# sb-sonata-headers1.net
KiCad netlist of a schematic drawn in Altium Designer
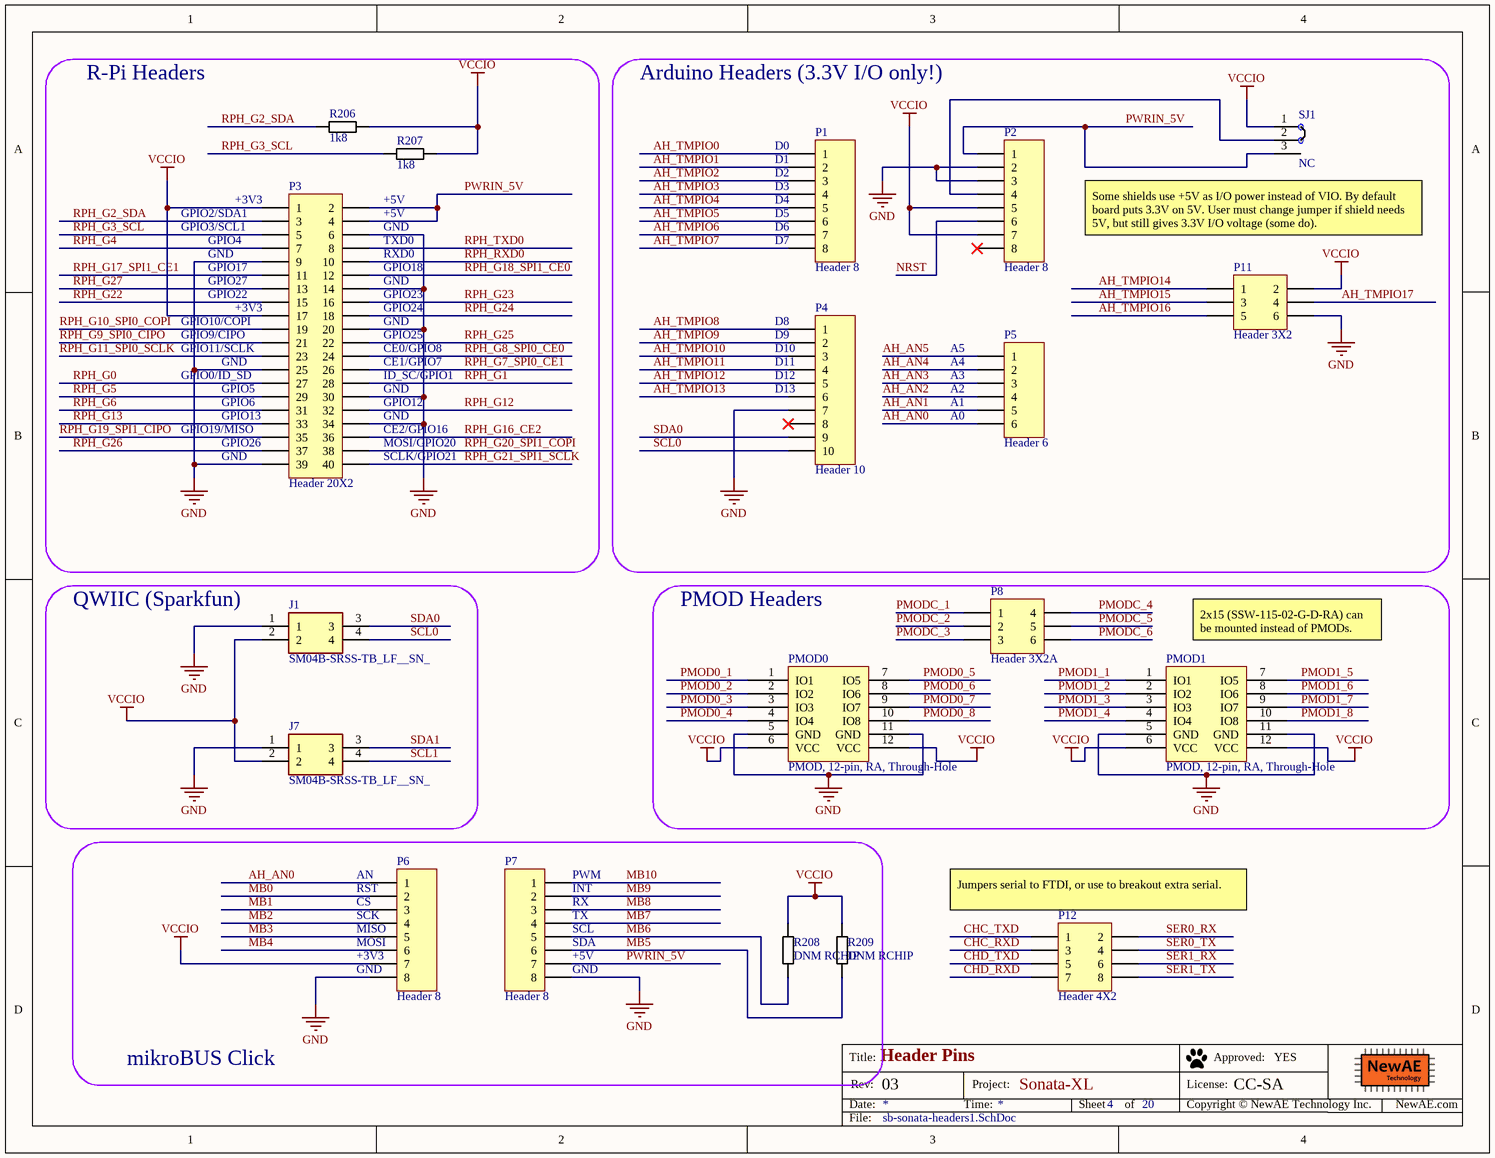
[diagram p0: sb-sonata-headers1.SchDoc]

(export (version "E")
  (design (tool "Eeschema 10.0.6"))
  (components
    (comp (ref "J1")
      (value "SM04B-SRSS-TB_LF__SN_")
      (footprint "SM04B-SRSS-TB(LFSN)")
      (description "Connector")
      (fields (field (name "MANUFACTURER_PART_NUMBER") "SM04B-SRSS-TB(LF)(SN)"))
      (libsource (lib "*") (part "SM04B-SRSS-TB_LF__SN_"))
    )
    (comp (ref "J7")
      (value "SM04B-SRSS-TB_LF__SN_")
      (footprint "SM04B-SRSS-TB(LFSN)")
      (description "Connector")
      (fields (field (name "MANUFACTURER_PART_NUMBER") "SM04B-SRSS-TB(LF)(SN)"))
      (libsource (lib "*") (part "SM04B-SRSS-TB_LF__SN_"))
    )
    (comp (ref "P1")
      (value "Header 8")
      (footprint "HDR1X8_SLW-108-01-T-S")
      (description "Header, 8-Pin")
      (fields (field (name "PUBLISHER") "Altium Limited"))
      (libsource (lib "Miscellaneous Connectors") (part "Header 8"))
    )
    (comp (ref "P2")
      (value "Header 8")
      (footprint "HDR1X8_SLW-108-01-T-S")
      (description "Header, 8-Pin")
      (fields (field (name "PUBLISHER") "Altium Limited"))
      (libsource (lib "Miscellaneous Connectors") (part "Header 8"))
    )
    (comp (ref "P3")
      (value "Header 20X2")
      (footprint "HDR2X20_861400402YO2LF")
      (description "Header, 20-Pin, Dual row")
      (fields (field (name "PUBLISHER") "Altium Limited"))
      (libsource (lib "Miscellaneous Connectors") (part "Header 20X2"))
    )
    (comp (ref "P4")
      (value "Header 10")
      (footprint "HDR1X10_SLW-110-01-T-S")
      (description "Header, 10-Pin")
      (fields (field (name "PUBLISHER") "Altium Limited"))
      (libsource (lib "Miscellaneous Connectors") (part "Header 10"))
    )
    (comp (ref "P5")
      (value "Header 6")
      (footprint "HDR1X6_SLW-106-01-T-S")
      (description "Header, 6-Pin")
      (fields (field (name "PUBLISHER") "Altium Limited"))
      (libsource (lib "Miscellaneous Connectors") (part "Header 6"))
    )
    (comp (ref "P6")
      (value "Header 8")
      (footprint "HDR1X8_SLW-108-01-T-S")
      (description "Header, 8-Pin")
      (fields (field (name "PUBLISHER") "Altium Limited"))
      (libsource (lib "Miscellaneous Connectors") (part "Header 8"))
    )
    (comp (ref "P7")
      (value "Header 8")
      (footprint "HDR1X8_SLW-108-01-T-S")
      (description "Header, 8-Pin")
      (fields (field (name "PUBLISHER") "Altium Limited"))
      (libsource (lib "") (part "Header 8_1"))
    )
    (comp (ref "P8")
      (value "Header 3X2A")
      (footprint "HDR2X3_CEN")
      (description "Header, 3-Pin, Dual row")
      (fields (field (name "PUBLISHER") "Altium Limited"))
      (libsource (lib "Miscellaneous Connectors") (part "Header 3X2A"))
    )
    (comp (ref "P11")
      (value "Header 3X2")
      (footprint "HDR2X3_XG8T-0641")
      (description "Header, 3-Pin, Dual row")
      (fields (field (name "PUBLISHER") "Altium Limited"))
      (libsource (lib "Miscellaneous Connectors") (part "Header 3X2"))
    )
    (comp (ref "P12")
      (value "Header 4X2")
      (footprint "HDR2X4_XG8T-0841")
      (description "Header, 4-Pin, Dual row")
      (fields (field (name "PUBLISHER") "Altium Limited"))
      (libsource (lib "Miscellaneous Connectors") (part "Header 4X2"))
    )
    (comp (ref "PMOD0")
      (value "PMOD, 12-pin, RA, Through-Hole")
      (footprint "SAMTEC_SSW_106_02_X_D_RA_PMOD")
      (fields (field (name "PART NUMBER") "PMOD_2ROW_FEMALERATH"))
      (libsource (lib "NewAE_AltiumLib") (part "12PIN_RA_FEMALE"))
    )
    (comp (ref "PMOD1")
      (value "PMOD, 12-pin, RA, Through-Hole")
      (footprint "SAMTEC_SSW_106_02_X_D_RA_PMOD")
      (fields (field (name "PART NUMBER") "PMOD_2ROW_FEMALERATH"))
      (libsource (lib "NewAE_AltiumLib") (part "12PIN_RA_FEMALE"))
    )
    (comp (ref "R206")
      (value "1k8")
      (footprint "RESC1608X55N")
      (description "1k8 res, 0603, 1%, 1/10W")
      (fields (field (name "PART NUMBER") "RCHIP-1K8-0603") (field (name "TOLERANCE") "1%"))
      (libsource (lib "") (part "RES-EU_1"))
    )
    (comp (ref "R207")
      (value "1k8")
      (footprint "RESC1608X55N")
      (description "1k8 res, 0603, 1%, 1/10W")
      (fields (field (name "PART NUMBER") "RCHIP-1K8-0603") (field (name "TOLERANCE") "1%"))
      (libsource (lib "") (part "RES-EU_1"))
    )
    (comp (ref "R208")
      (value "DNM RCHIP")
      (footprint "RESC1608X55N")
      (description "Do Not Mount Resistor")
      (fields (field (name "PART NUMBER") "RCHIP-DNM-0603"))
      (libsource (lib "NewAE_AltiumLib") (part "RES-EU"))
    )
    (comp (ref "R209")
      (value "DNM RCHIP")
      (footprint "RESC1608X55N")
      (description "Do Not Mount Resistor")
      (fields (field (name "PART NUMBER") "RCHIP-DNM-0603"))
      (libsource (lib "NewAE_AltiumLib") (part "RES-EU"))
    )
    (comp (ref "SJ1")
      (value "NC")
      (footprint "SJ_3S_NC12")
      (description "Solder Jumper, NC")
      (fields (field (name "PART NUMBER") "SJ_3S_12JMP"))
      (libsource (lib "NewAE_AltiumLib") (part "SJ_3S_12JMP"))
    )
  )
  (nets
    (net (code "1") (name "/AH_AN0") (class "Default")
      (node (ref "P5") (pin "6") (pinfunction "6_6") (pintype "passive"))
      (node (ref "P6") (pin "1") (pinfunction "1_1") (pintype "passive"))
    )
    (net (code "2") (name "/AH_AN1") (class "Default")
      (node (ref "P5") (pin "5") (pinfunction "5_5") (pintype "passive"))
    )
    (net (code "3") (name "/AH_AN2") (class "Default")
      (node (ref "P5") (pin "4") (pinfunction "4_4") (pintype "passive"))
    )
    (net (code "4") (name "/AH_AN3") (class "Default")
      (node (ref "P5") (pin "3") (pinfunction "3_3") (pintype "passive"))
    )
    (net (code "5") (name "/AH_AN4") (class "Default")
      (node (ref "P5") (pin "2") (pinfunction "2_2") (pintype "passive"))
    )
    (net (code "6") (name "/AH_AN5") (class "Default")
      (node (ref "P5") (pin "1") (pinfunction "1_1") (pintype "passive"))
    )
    (net (code "7") (name "/AH_TMPIO0") (class "Default")
      (node (ref "P1") (pin "1") (pinfunction "1_1") (pintype "passive"))
    )
    (net (code "8") (name "/AH_TMPIO1") (class "Default")
      (node (ref "P1") (pin "2") (pinfunction "2_2") (pintype "passive"))
    )
    (net (code "9") (name "/AH_TMPIO2") (class "Default")
      (node (ref "P1") (pin "3") (pinfunction "3_3") (pintype "passive"))
    )
    (net (code "10") (name "/AH_TMPIO3") (class "Default")
      (node (ref "P1") (pin "4") (pinfunction "4_4") (pintype "passive"))
    )
    (net (code "11") (name "/AH_TMPIO4") (class "Default")
      (node (ref "P1") (pin "5") (pinfunction "5_5") (pintype "passive"))
    )
    (net (code "12") (name "/AH_TMPIO5") (class "Default")
      (node (ref "P1") (pin "6") (pinfunction "6_6") (pintype "passive"))
    )
    (net (code "13") (name "/AH_TMPIO6") (class "Default")
      (node (ref "P1") (pin "7") (pinfunction "7_7") (pintype "passive"))
    )
    (net (code "14") (name "/AH_TMPIO7") (class "Default")
      (node (ref "P1") (pin "8") (pinfunction "8_8") (pintype "passive"))
    )
    (net (code "15") (name "/AH_TMPIO8") (class "Default")
      (node (ref "P4") (pin "1") (pinfunction "1_1") (pintype "passive"))
    )
    (net (code "16") (name "/AH_TMPIO9") (class "Default")
      (node (ref "P4") (pin "2") (pinfunction "2_2") (pintype "passive"))
    )
    (net (code "17") (name "/AH_TMPIO10") (class "Default")
      (node (ref "P4") (pin "3") (pinfunction "3_3") (pintype "passive"))
    )
    (net (code "18") (name "/AH_TMPIO11") (class "Default")
      (node (ref "P4") (pin "4") (pinfunction "4_4") (pintype "passive"))
    )
    (net (code "19") (name "/AH_TMPIO12") (class "Default")
      (node (ref "P4") (pin "5") (pinfunction "5_5") (pintype "passive"))
    )
    (net (code "20") (name "/AH_TMPIO13") (class "Default")
      (node (ref "P4") (pin "6") (pinfunction "6_6") (pintype "passive"))
    )
    (net (code "21") (name "/AH_TMPIO14") (class "Default")
      (node (ref "P11") (pin "1") (pinfunction "1_1") (pintype "passive"))
    )
    (net (code "22") (name "/AH_TMPIO15") (class "Default")
      (node (ref "P11") (pin "3") (pinfunction "3_3") (pintype "passive"))
    )
    (net (code "23") (name "/AH_TMPIO16") (class "Default")
      (node (ref "P11") (pin "5") (pinfunction "5_5") (pintype "passive"))
    )
    (net (code "24") (name "/AH_TMPIO17") (class "Default")
      (node (ref "P11") (pin "4") (pinfunction "4_4") (pintype "passive"))
    )
    (net (code "25") (name "/CHC_RXD") (class "Default")
      (node (ref "P12") (pin "3") (pinfunction "3_3") (pintype "passive"))
    )
    (net (code "26") (name "/CHC_TXD") (class "Default")
      (node (ref "P12") (pin "1") (pinfunction "1_1") (pintype "passive"))
    )
    (net (code "27") (name "/CHD_RXD") (class "Default")
      (node (ref "P12") (pin "7") (pinfunction "7_7") (pintype "passive"))
    )
    (net (code "28") (name "/CHD_TXD") (class "Default")
      (node (ref "P12") (pin "5") (pinfunction "5_5") (pintype "passive"))
    )
    (net (code "29") (name "/MB0") (class "Default")
      (node (ref "P6") (pin "2") (pinfunction "2_2") (pintype "passive"))
    )
    (net (code "30") (name "/MB1") (class "Default")
      (node (ref "P6") (pin "3") (pinfunction "3_3") (pintype "passive"))
    )
    (net (code "31") (name "/MB2") (class "Default")
      (node (ref "P6") (pin "4") (pinfunction "4_4") (pintype "passive"))
    )
    (net (code "32") (name "/MB3") (class "Default")
      (node (ref "P6") (pin "5") (pinfunction "5_5") (pintype "passive"))
    )
    (net (code "33") (name "/MB4") (class "Default")
      (node (ref "P6") (pin "6") (pinfunction "6_6") (pintype "passive"))
    )
    (net (code "34") (name "/MB5") (class "Default")
      (node (ref "P7") (pin "6") (pinfunction "6_6") (pintype "passive"))
      (node (ref "R209") (pin "2") (pinfunction "2_2") (pintype "passive"))
    )
    (net (code "35") (name "/MB6") (class "Default")
      (node (ref "P7") (pin "5") (pinfunction "5_5") (pintype "passive"))
      (node (ref "R208") (pin "2") (pinfunction "2_2") (pintype "passive"))
    )
    (net (code "36") (name "/MB7") (class "Default")
      (node (ref "P7") (pin "4") (pinfunction "4_4") (pintype "passive"))
    )
    (net (code "37") (name "/MB8") (class "Default")
      (node (ref "P7") (pin "3") (pinfunction "3_3") (pintype "passive"))
    )
    (net (code "38") (name "/MB9") (class "Default")
      (node (ref "P7") (pin "2") (pinfunction "2_2") (pintype "passive"))
    )
    (net (code "39") (name "/MB10") (class "Default")
      (node (ref "P7") (pin "1") (pinfunction "1_1") (pintype "passive"))
    )
    (net (code "40") (name "/NRST") (class "Default")
      (node (ref "P2") (pin "6") (pinfunction "6_6") (pintype "passive"))
    )
    (net (code "41") (name "/PMOD0_1") (class "Default")
      (node (ref "PMOD0") (pin "1") (pinfunction "IO1_1") (pintype "passive"))
    )
    (net (code "42") (name "/PMOD0_2") (class "Default")
      (node (ref "PMOD0") (pin "2") (pinfunction "IO2_2") (pintype "passive"))
    )
    (net (code "43") (name "/PMOD0_3") (class "Default")
      (node (ref "PMOD0") (pin "3") (pinfunction "IO3_3") (pintype "passive"))
    )
    (net (code "44") (name "/PMOD0_4") (class "Default")
      (node (ref "PMOD0") (pin "4") (pinfunction "IO4_4") (pintype "passive"))
    )
    (net (code "45") (name "/PMOD0_5") (class "Default")
      (node (ref "PMOD0") (pin "7") (pinfunction "IO5_7") (pintype "passive"))
    )
    (net (code "46") (name "/PMOD0_6") (class "Default")
      (node (ref "PMOD0") (pin "8") (pinfunction "IO6_8") (pintype "passive"))
    )
    (net (code "47") (name "/PMOD0_7") (class "Default")
      (node (ref "PMOD0") (pin "9") (pinfunction "IO7_9") (pintype "passive"))
    )
    (net (code "48") (name "/PMOD0_8") (class "Default")
      (node (ref "PMOD0") (pin "10") (pinfunction "IO8_10") (pintype "passive"))
    )
    (net (code "49") (name "/PMOD1_1") (class "Default")
      (node (ref "PMOD1") (pin "1") (pinfunction "IO1_1") (pintype "passive"))
    )
    (net (code "50") (name "/PMOD1_2") (class "Default")
      (node (ref "PMOD1") (pin "2") (pinfunction "IO2_2") (pintype "passive"))
    )
    (net (code "51") (name "/PMOD1_3") (class "Default")
      (node (ref "PMOD1") (pin "3") (pinfunction "IO3_3") (pintype "passive"))
    )
    (net (code "52") (name "/PMOD1_4") (class "Default")
      (node (ref "PMOD1") (pin "4") (pinfunction "IO4_4") (pintype "passive"))
    )
    (net (code "53") (name "/PMOD1_5") (class "Default")
      (node (ref "PMOD1") (pin "7") (pinfunction "IO5_7") (pintype "passive"))
    )
    (net (code "54") (name "/PMOD1_6") (class "Default")
      (node (ref "PMOD1") (pin "8") (pinfunction "IO6_8") (pintype "passive"))
    )
    (net (code "55") (name "/PMOD1_7") (class "Default")
      (node (ref "PMOD1") (pin "9") (pinfunction "IO7_9") (pintype "passive"))
    )
    (net (code "56") (name "/PMOD1_8") (class "Default")
      (node (ref "PMOD1") (pin "10") (pinfunction "IO8_10") (pintype "passive"))
    )
    (net (code "57") (name "/PMODC_1") (class "Default")
      (node (ref "P8") (pin "1") (pinfunction "1_1") (pintype "passive"))
    )
    (net (code "58") (name "/PMODC_2") (class "Default")
      (node (ref "P8") (pin "2") (pinfunction "2_2") (pintype "passive"))
    )
    (net (code "59") (name "/PMODC_3") (class "Default")
      (node (ref "P8") (pin "3") (pinfunction "3_3") (pintype "passive"))
    )
    (net (code "60") (name "/PMODC_4") (class "Default")
      (node (ref "P8") (pin "4") (pinfunction "4_4") (pintype "passive"))
    )
    (net (code "61") (name "/PMODC_5") (class "Default")
      (node (ref "P8") (pin "5") (pinfunction "5_5") (pintype "passive"))
    )
    (net (code "62") (name "/PMODC_6") (class "Default")
      (node (ref "P8") (pin "6") (pinfunction "6_6") (pintype "passive"))
    )
    (net (code "63") (name "/PWRIN_5V") (class "Default")
      (node (ref "P2") (pin "1") (pinfunction "1_1") (pintype "passive"))
      (node (ref "P3") (pin "2") (pinfunction "2_2") (pintype "passive"))
      (node (ref "P3") (pin "4") (pinfunction "4_4") (pintype "passive"))
      (node (ref "P7") (pin "7") (pinfunction "7_7") (pintype "passive"))
      (node (ref "SJ1") (pin "3") (pinfunction "3_3") (pintype "passive"))
    )
    (net (code "64") (name "/RPH_G0") (class "Default")
      (node (ref "P3") (pin "27") (pinfunction "27_27") (pintype "passive"))
    )
    (net (code "65") (name "/RPH_G1") (class "Default")
      (node (ref "P3") (pin "28") (pinfunction "28_28") (pintype "passive"))
    )
    (net (code "66") (name "/RPH_G2_SDA") (class "Default")
      (node (ref "P3") (pin "3") (pinfunction "3_3") (pintype "passive"))
      (node (ref "R206") (pin "1") (pinfunction "1_1") (pintype "passive"))
    )
    (net (code "67") (name "/RPH_G3_SCL") (class "Default")
      (node (ref "P3") (pin "5") (pinfunction "5_5") (pintype "passive"))
      (node (ref "R207") (pin "1") (pinfunction "1_1") (pintype "passive"))
    )
    (net (code "68") (name "/RPH_G4") (class "Default")
      (node (ref "P3") (pin "7") (pinfunction "7_7") (pintype "passive"))
    )
    (net (code "69") (name "/RPH_G5") (class "Default")
      (node (ref "P3") (pin "29") (pinfunction "29_29") (pintype "passive"))
    )
    (net (code "70") (name "/RPH_G6") (class "Default")
      (node (ref "P3") (pin "31") (pinfunction "31_31") (pintype "passive"))
    )
    (net (code "71") (name "/RPH_G7_SPI0_CE1") (class "Default")
      (node (ref "P3") (pin "26") (pinfunction "26_26") (pintype "passive"))
    )
    (net (code "72") (name "/RPH_G8_SPI0_CE0") (class "Default")
      (node (ref "P3") (pin "24") (pinfunction "24_24") (pintype "passive"))
    )
    (net (code "73") (name "/RPH_G9_SPI0_CIPO") (class "Default")
      (node (ref "P3") (pin "21") (pinfunction "21_21") (pintype "passive"))
    )
    (net (code "74") (name "/RPH_G10_SPI0_COPI") (class "Default")
      (node (ref "P3") (pin "19") (pinfunction "19_19") (pintype "passive"))
    )
    (net (code "75") (name "/RPH_G11_SPI0_SCLK") (class "Default")
      (node (ref "P3") (pin "23") (pinfunction "23_23") (pintype "passive"))
    )
    (net (code "76") (name "/RPH_G12") (class "Default")
      (node (ref "P3") (pin "32") (pinfunction "32_32") (pintype "passive"))
    )
    (net (code "77") (name "/RPH_G13") (class "Default")
      (node (ref "P3") (pin "33") (pinfunction "33_33") (pintype "passive"))
    )
    (net (code "78") (name "/RPH_G16_CE2") (class "Default")
      (node (ref "P3") (pin "36") (pinfunction "36_36") (pintype "passive"))
    )
    (net (code "79") (name "/RPH_G17_SPI1_CE1") (class "Default")
      (node (ref "P3") (pin "11") (pinfunction "11_11") (pintype "passive"))
    )
    (net (code "80") (name "/RPH_G18_SPI1_CE0") (class "Default")
      (node (ref "P3") (pin "12") (pinfunction "12_12") (pintype "passive"))
    )
    (net (code "81") (name "/RPH_G19_SPI1_CIPO") (class "Default")
      (node (ref "P3") (pin "35") (pinfunction "35_35") (pintype "passive"))
    )
    (net (code "82") (name "/RPH_G20_SPI1_COPI") (class "Default")
      (node (ref "P3") (pin "38") (pinfunction "38_38") (pintype "passive"))
    )
    (net (code "83") (name "/RPH_G21_SPI1_SCLK") (class "Default")
      (node (ref "P3") (pin "40") (pinfunction "40_40") (pintype "passive"))
    )
    (net (code "84") (name "/RPH_G22") (class "Default")
      (node (ref "P3") (pin "15") (pinfunction "15_15") (pintype "passive"))
    )
    (net (code "85") (name "/RPH_G23") (class "Default")
      (node (ref "P3") (pin "16") (pinfunction "16_16") (pintype "passive"))
    )
    (net (code "86") (name "/RPH_G24") (class "Default")
      (node (ref "P3") (pin "18") (pinfunction "18_18") (pintype "passive"))
    )
    (net (code "87") (name "/RPH_G25") (class "Default")
      (node (ref "P3") (pin "22") (pinfunction "22_22") (pintype "passive"))
    )
    (net (code "88") (name "/RPH_G26") (class "Default")
      (node (ref "P3") (pin "37") (pinfunction "37_37") (pintype "passive"))
    )
    (net (code "89") (name "/RPH_G27") (class "Default")
      (node (ref "P3") (pin "13") (pinfunction "13_13") (pintype "passive"))
    )
    (net (code "90") (name "/RPH_RXD0") (class "Default")
      (node (ref "P3") (pin "10") (pinfunction "10_10") (pintype "passive"))
    )
    (net (code "91") (name "/RPH_TXD0") (class "Default")
      (node (ref "P3") (pin "8") (pinfunction "8_8") (pintype "passive"))
    )
    (net (code "92") (name "/SCL0") (class "Default")
      (node (ref "J1") (pin "4") (pinfunction "4_4") (pintype "passive"))
      (node (ref "P4") (pin "10") (pinfunction "10_10") (pintype "passive"))
    )
    (net (code "93") (name "/SCL1") (class "Default")
      (node (ref "J7") (pin "4") (pinfunction "4_4") (pintype "passive"))
    )
    (net (code "94") (name "/SDA0") (class "Default")
      (node (ref "J1") (pin "3") (pinfunction "3_3") (pintype "passive"))
      (node (ref "P4") (pin "9") (pinfunction "9_9") (pintype "passive"))
    )
    (net (code "95") (name "/SDA1") (class "Default")
      (node (ref "J7") (pin "3") (pinfunction "3_3") (pintype "passive"))
    )
    (net (code "96") (name "/SER0_RX") (class "Default")
      (node (ref "P12") (pin "2") (pinfunction "2_2") (pintype "passive"))
    )
    (net (code "97") (name "/SER0_TX") (class "Default")
      (node (ref "P12") (pin "4") (pinfunction "4_4") (pintype "passive"))
    )
    (net (code "98") (name "/SER1_RX") (class "Default")
      (node (ref "P12") (pin "6") (pinfunction "6_6") (pintype "passive"))
    )
    (net (code "99") (name "/SER1_TX") (class "Default")
      (node (ref "P12") (pin "8") (pinfunction "8_8") (pintype "passive"))
    )
    (net (code "100") (name "GND") (class "Default")
      (node (ref "J1") (pin "1") (pinfunction "1_1") (pintype "passive"))
      (node (ref "J7") (pin "1") (pinfunction "1_1") (pintype "passive"))
      (node (ref "P11") (pin "6") (pinfunction "6_6") (pintype "passive"))
      (node (ref "P2") (pin "2") (pinfunction "2_2") (pintype "passive"))
      (node (ref "P2") (pin "3") (pinfunction "3_3") (pintype "passive"))
      (node (ref "P3") (pin "14") (pinfunction "14_14") (pintype "passive"))
      (node (ref "P3") (pin "20") (pinfunction "20_20") (pintype "passive"))
      (node (ref "P3") (pin "25") (pinfunction "25_25") (pintype "passive"))
      (node (ref "P3") (pin "30") (pinfunction "30_30") (pintype "passive"))
      (node (ref "P3") (pin "34") (pinfunction "34_34") (pintype "passive"))
      (node (ref "P3") (pin "39") (pinfunction "39_39") (pintype "passive"))
      (node (ref "P3") (pin "6") (pinfunction "6_6") (pintype "passive"))
      (node (ref "P3") (pin "9") (pinfunction "9_9") (pintype "passive"))
      (node (ref "P4") (pin "7") (pinfunction "7_7") (pintype "passive"))
      (node (ref "P6") (pin "8") (pinfunction "8_8") (pintype "passive"))
      (node (ref "P7") (pin "8") (pinfunction "8_8") (pintype "passive"))
      (node (ref "PMOD0") (pin "11") (pinfunction "GND_11") (pintype "passive"))
      (node (ref "PMOD0") (pin "5") (pinfunction "GND_5") (pintype "passive"))
      (node (ref "PMOD1") (pin "11") (pinfunction "GND_11") (pintype "passive"))
      (node (ref "PMOD1") (pin "5") (pinfunction "GND_5") (pintype "passive"))
    )
    (net (code "101") (name "Net-(P2-Pad4)") (class "Default")
      (node (ref "P2") (pin "4") (pinfunction "4_4") (pintype "passive"))
      (node (ref "SJ1") (pin "2") (pinfunction "2_2") (pintype "passive"))
    )
    (net (code "102") (name "VCCIO") (class "Default")
      (node (ref "J1") (pin "2") (pinfunction "2_2") (pintype "passive"))
      (node (ref "J7") (pin "2") (pinfunction "2_2") (pintype "passive"))
      (node (ref "P11") (pin "2") (pinfunction "2_2") (pintype "passive"))
      (node (ref "P2") (pin "5") (pinfunction "5_5") (pintype "passive"))
      (node (ref "P2") (pin "7") (pinfunction "7_7") (pintype "passive"))
      (node (ref "P3") (pin "1") (pinfunction "1_1") (pintype "passive"))
      (node (ref "P3") (pin "17") (pinfunction "17_17") (pintype "passive"))
      (node (ref "P6") (pin "7") (pinfunction "7_7") (pintype "passive"))
      (node (ref "PMOD0") (pin "12") (pinfunction "VCC_12") (pintype "passive"))
      (node (ref "PMOD0") (pin "6") (pinfunction "VCC_6") (pintype "passive"))
      (node (ref "PMOD1") (pin "12") (pinfunction "VCC_12") (pintype "passive"))
      (node (ref "PMOD1") (pin "6") (pinfunction "VCC_6") (pintype "passive"))
      (node (ref "R206") (pin "2") (pinfunction "2_2") (pintype "passive"))
      (node (ref "R207") (pin "2") (pinfunction "2_2") (pintype "passive"))
      (node (ref "R208") (pin "1") (pinfunction "1_1") (pintype "passive"))
      (node (ref "R209") (pin "1") (pinfunction "1_1") (pintype "passive"))
      (node (ref "SJ1") (pin "1") (pinfunction "1_1") (pintype "passive"))
    )
    (net (code "103") (name "unconnected-(P2-Pad8)") (class "Default")
      (node (ref "P2") (pin "8") (pinfunction "8_8") (pintype "passive+no_connect"))
    )
    (net (code "104") (name "unconnected-(P4-Pad8)") (class "Default")
      (node (ref "P4") (pin "8") (pinfunction "8_8") (pintype "passive+no_connect"))
    )
  )
)
